# AstroEQ_PTH_V4_6.net
KiCad netlist of a schematic drawn in EAGLE
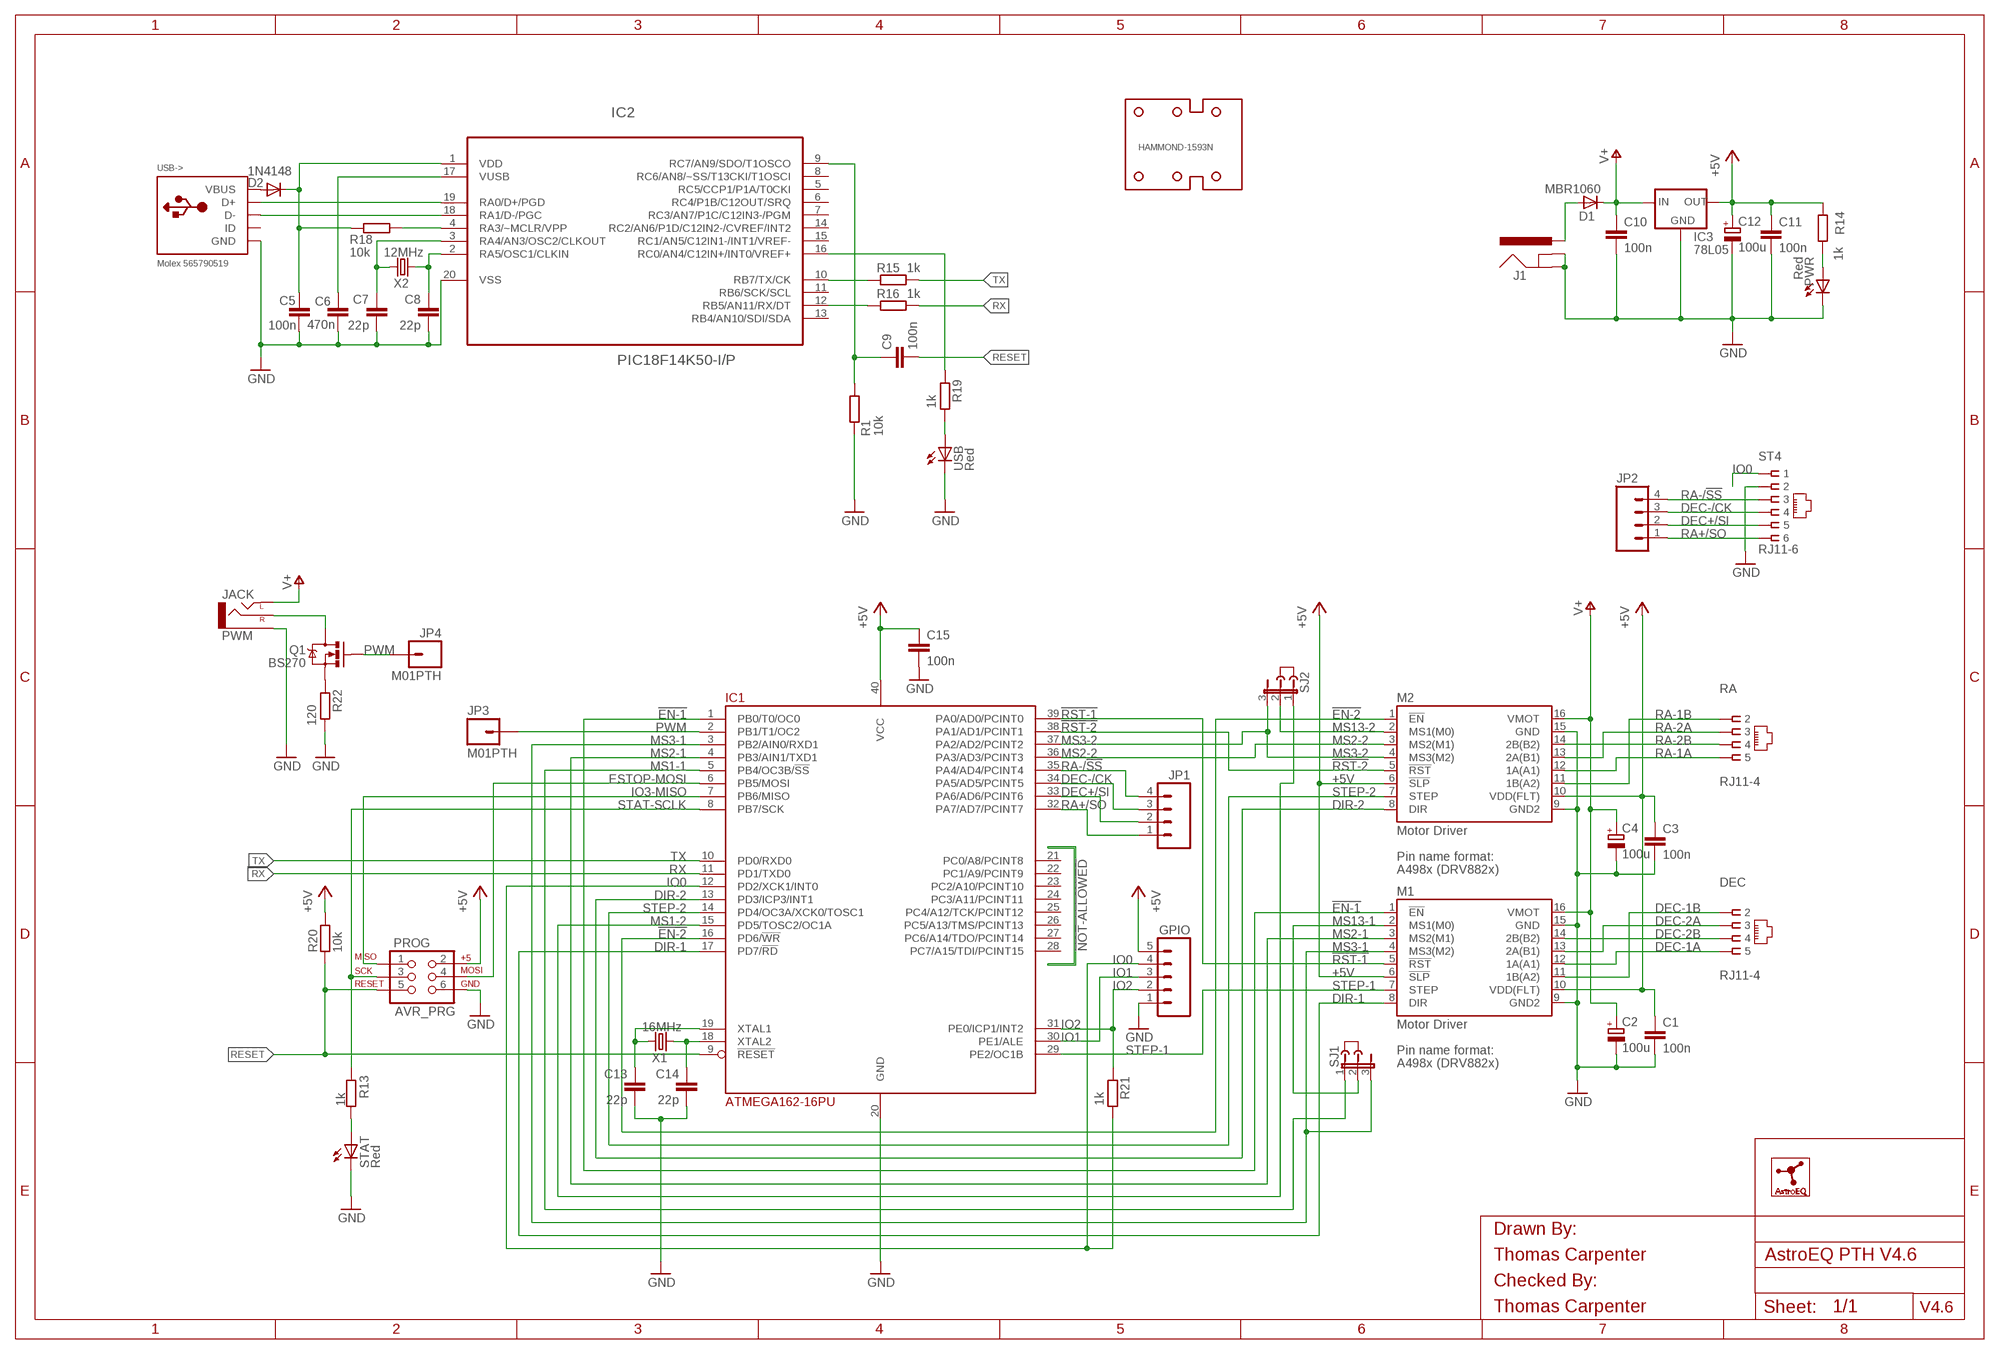
[diagram p0: schematic, sheet 1]

(export (version "E")
  (design (tool "Eeschema 10.0.6"))
  (components
    (comp (ref "C1")
      (value "100n")
      (footprint "eagle-import:C025-024X044")
      (fields (field (name "MF") "AVX") (field (name "MPN") "SR205C104KAR"))
      (libsource (lib "eagle-import") (part "C-EU025-024X044"))
    )
    (comp (ref "C2")
      (value "100u")
      (footprint "eagle-import:E2,5-7")
      (fields (field (name "MF") "MULTICOMP") (field (name "MPN") "MCGPR25V107M6.3X11"))
      (libsource (lib "eagle-import") (part "CPOL-EUE2.5-7"))
    )
    (comp (ref "C3")
      (value "100n")
      (footprint "eagle-import:C025-024X044")
      (fields (field (name "MF") "AVX") (field (name "MPN") "SR205C104KAR"))
      (libsource (lib "eagle-import") (part "C-EU025-024X044"))
    )
    (comp (ref "C4")
      (value "100u")
      (footprint "eagle-import:E2,5-7")
      (fields (field (name "MF") "MULTICOMP") (field (name "MPN") "MCGPR25V107M6.3X11"))
      (libsource (lib "eagle-import") (part "CPOL-EUE2.5-7"))
    )
    (comp (ref "C5")
      (value "100n")
      (footprint "eagle-import:C025-024X044")
      (fields (field (name "MF") "AVX") (field (name "MPN") "SR205C104KAR"))
      (libsource (lib "eagle-import") (part "C-EU025-024X044"))
    )
    (comp (ref "C6")
      (value "470n")
      (footprint "eagle-import:C025-024X044")
      (fields (field (name "MF") "KEMET") (field (name "MPN") "C320C474M5U5TA"))
      (libsource (lib "eagle-import") (part "C-EU025-024X044"))
    )
    (comp (ref "C7")
      (value "22p")
      (footprint "eagle-import:C025-024X044")
      (fields (field (name "MF") "AVX") (field (name "MPN") "SR151A220JAR"))
      (libsource (lib "eagle-import") (part "C-EU025-024X044"))
    )
    (comp (ref "C8")
      (value "22p")
      (footprint "eagle-import:C025-024X044")
      (fields (field (name "MF") "AVX") (field (name "MPN") "SR151A220JAR"))
      (libsource (lib "eagle-import") (part "C-EU025-024X044"))
    )
    (comp (ref "C9")
      (value "100n")
      (footprint "eagle-import:C025-024X044")
      (fields (field (name "MF") "AVX") (field (name "MPN") "SR205C104KAR"))
      (libsource (lib "eagle-import") (part "C-EU025-024X044"))
    )
    (comp (ref "C10")
      (value "100n")
      (footprint "eagle-import:C025-024X044")
      (fields (field (name "MF") "AVX") (field (name "MPN") "SR205C104KAR"))
      (libsource (lib "eagle-import") (part "C-EU025-024X044"))
    )
    (comp (ref "C11")
      (value "100n")
      (footprint "eagle-import:C025-024X044")
      (fields (field (name "MF") "AVX") (field (name "MPN") "SR205C104KAR"))
      (libsource (lib "eagle-import") (part "C-EU025-024X044"))
    )
    (comp (ref "C12")
      (value "100u")
      (footprint "eagle-import:E2,5-7")
      (fields (field (name "MF") "MULTICOMP") (field (name "MPN") "MCGPR25V107M6.3X11"))
      (libsource (lib "eagle-import") (part "CPOL-EUE2.5-7"))
    )
    (comp (ref "C13")
      (value "22p")
      (footprint "eagle-import:C025-024X044")
      (fields (field (name "MF") "AVX") (field (name "MPN") "SR151A220JAR"))
      (libsource (lib "eagle-import") (part "C-EU025-024X044"))
    )
    (comp (ref "C14")
      (value "22p")
      (footprint "eagle-import:C025-024X044")
      (fields (field (name "MF") "AVX") (field (name "MPN") "SR151A220JAR"))
      (libsource (lib "eagle-import") (part "C-EU025-024X044"))
    )
    (comp (ref "C15")
      (value "100n")
      (footprint "eagle-import:C025-024X044")
      (fields (field (name "MF") "AVX") (field (name "MPN") "SR205C104KAR"))
      (libsource (lib "eagle-import") (part "C-EU025-024X044"))
    )
    (comp (ref "D1")
      (value "MBR1060")
      (footprint "eagle-import:C221B1A")
      (fields (field (name "MF") "MULTICOMP"))
      (libsource (lib "eagle-import") (part "MUR820"))
    )
    (comp (ref "D2")
      (value "1N4148")
      (footprint "eagle-import:DIODE-1N4148")
      (fields (field (name "MF") "MULTICOMP") (field (name "MPN") "1N4148."))
      (libsource (lib "eagle-import") (part "DIODE1N4148"))
    )
    (comp (ref "DEC")
      (value "RJ11-4")
      (footprint "eagle-import:RJ11-NO_SHIELD-4")
      (fields (field (name "MF") "MOLEX") (field (name "MPN") "95501-2641"))
      (libsource (lib "eagle-import") (part "RJ11-4"))
    )
    (comp (ref "GPIO")
      (value "M05PTH")
      (footprint "eagle-import:1X05")
      (fields (field (name "MF") "CYNERGY3") (field (name "MPN") "SSF211X050"))
      (libsource (lib "eagle-import") (part "M05PTH"))
    )
    (comp (ref "HAMMOND-1593N")
      (value "HAMMOND-1593N-4HOLE")
      (footprint "eagle-import:HAMMOND-1593N4HOLES")
      (fields (field (name "MF") "HAMMOND") (field (name "MPN") "1593NBK"))
      (libsource (lib "eagle-import") (part "HAMMOND-1593N-4HOLE"))
    )
    (comp (ref "IC1")
      (value "ATMEGA162-16PU")
      (footprint "eagle-import:DIL40")
      (fields (field (name "MF") "ATMEL"))
      (libsource (lib "eagle-import") (part "ATMEGA162-16PU"))
    )
    (comp (ref "IC2")
      (value "PIC18F14K50-I/P")
      (footprint "eagle-import:DIL20")
      (fields (field (name "MF") "MICROCHIP"))
      (libsource (lib "eagle-import") (part "PIC18F14K50-I/P"))
    )
    (comp (ref "IC3")
      (value "78L05")
      (footprint "eagle-import:TO-92")
      (fields (field (name "MF") "FAIRCHILD SEMICONDUCTOR") (field (name "MPN") "LM78L05ACZX"))
      (libsource (lib "eagle-import") (part "V_REG_78XXTO-92"))
    )
    (comp (ref "J1")
      (value "POWER_JACKPTH")
      (footprint "eagle-import:POWER_JACK_PTH")
      (fields (field (name "MF") "MULTICOMP") (field (name "MPN") "MJ-179PH"))
      (libsource (lib "eagle-import") (part "POWER_JACKPTH"))
    )
    (comp (ref "J2")
      (value "JUMPER")
      (footprint "eagle-import:JUMP")
      (libsource (lib "eagle-import") (part "JUMPER"))
    )
    (comp (ref "J3")
      (value "JUMPER")
      (footprint "eagle-import:JUMP")
      (libsource (lib "eagle-import") (part "JUMPER"))
    )
    (comp (ref "JP1")
      (value "M04PTH")
      (footprint "eagle-import:1X04")
      (libsource (lib "eagle-import") (part "M04PTH"))
    )
    (comp (ref "JP2")
      (value "M04PTH")
      (footprint "eagle-import:1X04")
      (libsource (lib "eagle-import") (part "M04PTH"))
    )
    (comp (ref "JP3")
      (value "M01PTH")
      (footprint "eagle-import:1X01")
      (libsource (lib "eagle-import") (part "M01PTH"))
    )
    (comp (ref "JP4")
      (value "M01PTH")
      (footprint "eagle-import:1X01")
      (libsource (lib "eagle-import") (part "M01PTH"))
    )
    (comp (ref "LOGO1")
      (value "ASTROEQ5MM")
      (footprint "eagle-import:ASTROEQ-SMALL")
      (libsource (lib "eagle-import") (part "ASTROEQ5MM"))
    )
    (comp (ref "M1")
      (value "Motor Driver")
      (footprint "eagle-import:DIP16-W")
      (fields (field (name "MF") "SAMTEC") (field (name "MPN") "CES-116-01-T-S"))
      (libsource (lib "eagle-import") (part "A4983CARRIER"))
    )
    (comp (ref "M2")
      (value "Motor Driver")
      (footprint "eagle-import:DIP16-W")
      (fields (field (name "MF") "SAMTEC") (field (name "MPN") "CES-116-01-T-S"))
      (libsource (lib "eagle-import") (part "A4983CARRIER"))
    )
    (comp (ref "PROG")
      (value "AVR_PRG")
      (footprint "eagle-import:2X3")
      (fields (field (name "MF") "TE CONNECTIVITY / AMP") (field (name "MPN") "826632-3"))
      (libsource (lib "eagle-import") (part "AVR_SPI_PRG_6PTH"))
    )
    (comp (ref "PWM")
      (value "JACK")
      (footprint "eagle-import:AUDIO-JACK")
      (fields (field (name "MF") "CLIFF ELECTRONIC COMPONENTS") (field (name "MPN") "FC68131"))
      (libsource (lib "eagle-import") (part "AUDIO-JACKPTH"))
    )
    (comp (ref "PWR")
      (value "Red")
      (footprint "eagle-import:LED3MM")
      (fields (field (name "MF") "KINGBRIGHT") (field (name "MPN") "L-424HDT"))
      (libsource (lib "eagle-import") (part "LED3MM"))
    )
    (comp (ref "Q1")
      (value "BS270")
      (footprint "eagle-import:TO-92")
      (fields (field (name "MF") "FAIRCHILD SEMICONDUCTOR"))
      (libsource (lib "eagle-import") (part "MOSFET-NCHANNELPTH"))
    )
    (comp (ref "R1")
      (value "10k")
      (footprint "eagle-import:0204_7")
      (fields (field (name "MF") "MULTICOMP") (field (name "MPN") "MF12 10K"))
      (libsource (lib "eagle-import") (part "R-EU_0204/7"))
    )
    (comp (ref "R13")
      (value "1k")
      (footprint "eagle-import:0204_7")
      (fields (field (name "MF") "MULTICOMP") (field (name "MPN") "MF12 1K"))
      (libsource (lib "eagle-import") (part "R-EU_0204/7"))
    )
    (comp (ref "R14")
      (value "1k")
      (footprint "eagle-import:0204_7")
      (fields (field (name "MF") "MULTICOMP") (field (name "MPN") "MF12 1K"))
      (libsource (lib "eagle-import") (part "R-EU_0204/7"))
    )
    (comp (ref "R15")
      (value "1k")
      (footprint "eagle-import:0204_7")
      (fields (field (name "MF") "MULTICOMP") (field (name "MPN") "MF12 1K"))
      (libsource (lib "eagle-import") (part "R-EU_0204/7"))
    )
    (comp (ref "R16")
      (value "1k")
      (footprint "eagle-import:0204_7")
      (fields (field (name "MF") "MULTICOMP") (field (name "MPN") "MF12 1K"))
      (libsource (lib "eagle-import") (part "R-EU_0204/7"))
    )
    (comp (ref "R18")
      (value "10k")
      (footprint "eagle-import:0204_7")
      (fields (field (name "MF") "MULTICOMP") (field (name "MPN") "MF12 10K"))
      (libsource (lib "eagle-import") (part "R-EU_0204/7"))
    )
    (comp (ref "R19")
      (value "1k")
      (footprint "eagle-import:0204_7")
      (fields (field (name "MF") "MULTICOMP") (field (name "MPN") "MF12 1K"))
      (libsource (lib "eagle-import") (part "R-EU_0204/7"))
    )
    (comp (ref "R20")
      (value "10k")
      (footprint "eagle-import:0204_7")
      (fields (field (name "MF") "MULTICOMP") (field (name "MPN") "MF12 10K"))
      (libsource (lib "eagle-import") (part "R-EU_0204/7"))
    )
    (comp (ref "R21")
      (value "1k")
      (footprint "eagle-import:0204_7")
      (fields (field (name "MF") "MULTICOMP") (field (name "MPN") "MF12 1K"))
      (libsource (lib "eagle-import") (part "R-EU_0204/7"))
    )
    (comp (ref "R22")
      (value "120")
      (footprint "eagle-import:0204_7")
      (fields (field (name "MF") "MULTICOMP") (field (name "MPN") "MF12 120R"))
      (libsource (lib "eagle-import") (part "R-EU_0204/7"))
    )
    (comp (ref "RA")
      (value "RJ11-4")
      (footprint "eagle-import:RJ11-NO_SHIELD-4")
      (fields (field (name "MF") "MOLEX") (field (name "MPN") "95501-2641"))
      (libsource (lib "eagle-import") (part "RJ11-4"))
    )
    (comp (ref "SJ1")
      (value "JP2E")
      (footprint "eagle-import:JP2")
      (libsource (lib "eagle-import") (part "JP2E"))
    )
    (comp (ref "SJ2")
      (value "JP2EL")
      (footprint "eagle-import:JP2L")
      (libsource (lib "eagle-import") (part "JP2EL"))
    )
    (comp (ref "ST4")
      (value "RJ11-6")
      (footprint "eagle-import:RJ11-NO_SHIELD")
      (fields
        (field (name "MF") "TYCO ELECTRONICS")
        (field (name "MPN") "RJ11-2L-B")
        (field (name "MF_1") "MOLEX")
        (field (name "MPN_1") "95501-2661")
        (field (name "OC_FARNELL") "1536490")
      )
      (libsource (lib "eagle-import") (part "RJ11-2L-B"))
    )
    (comp (ref "STAT")
      (value "Red")
      (footprint "eagle-import:LED3MM")
      (fields (field (name "MF") "KINGBRIGHT") (field (name "MPN") "L-424HDT"))
      (libsource (lib "eagle-import") (part "LED3MM"))
    )
    (comp (ref "USB")
      (value "Red")
      (footprint "eagle-import:LED3MM")
      (fields (field (name "MF") "KINGBRIGHT") (field (name "MPN") "L-424HDT"))
      (libsource (lib "eagle-import") (part "LED3MM"))
    )
    (comp (ref "USB->")
      (value "Molex 565790519")
      (footprint "eagle-import:USB-MINIB-THM-MOLEX")
      (fields (field (name "MF") "MOLEX") (field (name "MPN") "565790519"))
      (libsource (lib "eagle-import") (part "USBMOLEX"))
    )
    (comp (ref "X1")
      (value "16MHz")
      (footprint "eagle-import:HC49US")
      (fields (field (name "MF") "TXC") (field (name "MPN") "9B-16.000MEEJ-B"))
      (libsource (lib "eagle-import") (part "CRYSTALHC49US"))
    )
    (comp (ref "X2")
      (value "12MHz")
      (footprint "eagle-import:HC49US")
      (fields (field (name "MF") "TXC") (field (name "MPN") "9B-12.000MAAJ-B"))
      (libsource (lib "eagle-import") (part "CRYSTALHC49US"))
    )
  )
  (nets
    (net (code "1") (name "+5V") (class "Default")
      (node (ref "C1") (pin "1") (pinfunction "1_1") (pintype "passive"))
      (node (ref "C11") (pin "1") (pinfunction "1_1") (pintype "passive"))
      (node (ref "C12") (pin "+") (pinfunction "+_+") (pintype "passive"))
      (node (ref "C15") (pin "1") (pinfunction "1_1") (pintype "passive"))
      (node (ref "C3") (pin "1") (pinfunction "1_1") (pintype "passive"))
      (node (ref "GPIO") (pin "5") (pinfunction "5_5") (pintype "passive"))
      (node (ref "IC1") (pin "40") (pinfunction "VCC_40") (pintype "power_in"))
      (node (ref "IC3") (pin "1") (pinfunction "OUT_1") (pintype "power_in"))
      (node (ref "M1") (pin "10") (pinfunction "VDD(FLT)_10") (pintype "power_in"))
      (node (ref "M1") (pin "6") (pinfunction "~{SLP}_6") (pintype "input"))
      (node (ref "M2") (pin "10") (pinfunction "VDD(FLT)_10") (pintype "power_in"))
      (node (ref "M2") (pin "6") (pinfunction "~{SLP}_6") (pintype "input"))
      (node (ref "PROG") (pin "2") (pinfunction "2_2") (pintype "passive"))
      (node (ref "R14") (pin "1") (pinfunction "1_1") (pintype "passive"))
      (node (ref "R20") (pin "2") (pinfunction "2_2") (pintype "passive"))
    )
    (net (code "2") (name "/DEC+{slash}SI") (class "Default")
      (node (ref "IC1") (pin "33") (pinfunction "PA6/AD6/PCINT6_33") (pintype "bidirectional"))
      (node (ref "JP1") (pin "2") (pinfunction "2_2") (pintype "passive"))
      (node (ref "JP2") (pin "2") (pinfunction "2_2") (pintype "passive"))
      (node (ref "ST4") (pin "5") (pinfunction "5_5") (pintype "passive"))
    )
    (net (code "3") (name "/DEC-1A") (class "Default")
      (node (ref "DEC") (pin "5") (pinfunction "5_5") (pintype "passive"))
      (node (ref "M1") (pin "12") (pinfunction "1A(A1)_12") (pintype "output"))
    )
    (net (code "4") (name "/DEC-1B") (class "Default")
      (node (ref "DEC") (pin "2") (pinfunction "2_2") (pintype "passive"))
      (node (ref "M1") (pin "11") (pinfunction "1B(A2)_11") (pintype "output"))
    )
    (net (code "5") (name "/DEC-2A") (class "Default")
      (node (ref "DEC") (pin "3") (pinfunction "3_3") (pintype "passive"))
      (node (ref "M1") (pin "13") (pinfunction "2A(B1)_13") (pintype "output"))
    )
    (net (code "6") (name "/DEC-2B") (class "Default")
      (node (ref "DEC") (pin "4") (pinfunction "4_4") (pintype "passive"))
      (node (ref "M1") (pin "14") (pinfunction "2B(B2)_14") (pintype "output"))
    )
    (net (code "7") (name "/DEC-{slash}CK") (class "Default")
      (node (ref "IC1") (pin "34") (pinfunction "PA5/AD5/PCINT5_34") (pintype "bidirectional"))
      (node (ref "JP1") (pin "3") (pinfunction "3_3") (pintype "passive"))
      (node (ref "JP2") (pin "3") (pinfunction "3_3") (pintype "passive"))
      (node (ref "ST4") (pin "4") (pinfunction "4_4") (pintype "passive"))
    )
    (net (code "8") (name "/DIR-1") (class "Default")
      (node (ref "IC1") (pin "17") (pinfunction "PD7/~{RD}_17") (pintype "bidirectional"))
      (node (ref "M1") (pin "8") (pinfunction "DIR_8") (pintype "input"))
    )
    (net (code "9") (name "/DIR-2") (class "Default")
      (node (ref "IC1") (pin "13") (pinfunction "PD3/ICP3/INT1_13") (pintype "bidirectional"))
      (node (ref "M2") (pin "8") (pinfunction "DIR_8") (pintype "input"))
    )
    (net (code "10") (name "/ESTOP-MOSI") (class "Default")
      (node (ref "IC1") (pin "6") (pinfunction "PB5/MOSI_6") (pintype "bidirectional"))
      (node (ref "PROG") (pin "4") (pinfunction "4_4") (pintype "passive"))
    )
    (net (code "11") (name "/IO0") (class "Default")
      (node (ref "GPIO") (pin "4") (pinfunction "4_4") (pintype "passive"))
      (node (ref "IC1") (pin "12") (pinfunction "PD2/XCK1/INT0_12") (pintype "bidirectional"))
      (node (ref "R21") (pin "1") (pinfunction "1_1") (pintype "passive"))
      (node (ref "ST4") (pin "1") (pinfunction "1_1") (pintype "passive"))
    )
    (net (code "12") (name "/IO1") (class "Default")
      (node (ref "GPIO") (pin "3") (pinfunction "3_3") (pintype "passive"))
      (node (ref "IC1") (pin "30") (pinfunction "PE1/ALE_30") (pintype "bidirectional"))
    )
    (net (code "13") (name "/IO2") (class "Default")
      (node (ref "GPIO") (pin "2") (pinfunction "2_2") (pintype "passive"))
      (node (ref "IC1") (pin "31") (pinfunction "PE0/ICP1/INT2_31") (pintype "bidirectional"))
      (node (ref "R21") (pin "2") (pinfunction "2_2") (pintype "passive"))
    )
    (net (code "14") (name "/IO3-MISO") (class "Default")
      (node (ref "IC1") (pin "7") (pinfunction "PB6/MISO_7") (pintype "bidirectional"))
      (node (ref "PROG") (pin "1") (pinfunction "1_1") (pintype "passive"))
    )
    (net (code "15") (name "/MS1-1") (class "Default")
      (node (ref "IC1") (pin "5") (pinfunction "PB4/OC3B/~{SS}_5") (pintype "bidirectional"))
      (node (ref "SJ1") (pin "1") (pinfunction "1_1") (pintype "passive"))
    )
    (net (code "16") (name "/MS1-2") (class "Default")
      (node (ref "IC1") (pin "15") (pinfunction "PD5/TOSC2/OC1A_15") (pintype "bidirectional"))
      (node (ref "SJ2") (pin "1") (pinfunction "1_1") (pintype "passive"))
    )
    (net (code "17") (name "/MS2-1") (class "Default")
      (node (ref "IC1") (pin "4") (pinfunction "PB3/AIN1/TXD1_4") (pintype "bidirectional"))
      (node (ref "M1") (pin "3") (pinfunction "MS2(M1)_3") (pintype "input"))
    )
    (net (code "18") (name "/MS2-2") (class "Default")
      (node (ref "IC1") (pin "36") (pinfunction "PA3/AD3/PCINT3_36") (pintype "bidirectional"))
      (node (ref "M2") (pin "3") (pinfunction "MS2(M1)_3") (pintype "input"))
    )
    (net (code "19") (name "/MS3-1") (class "Default")
      (node (ref "IC1") (pin "3") (pinfunction "PB2/AIN0/RXD1_3") (pintype "bidirectional"))
      (node (ref "M1") (pin "4") (pinfunction "MS3(M2)_4") (pintype "input"))
      (node (ref "SJ1") (pin "3") (pinfunction "3_3") (pintype "passive"))
    )
    (net (code "20") (name "/MS3-2") (class "Default")
      (node (ref "IC1") (pin "37") (pinfunction "PA2/AD2/PCINT2_37") (pintype "bidirectional"))
      (node (ref "M2") (pin "4") (pinfunction "MS3(M2)_4") (pintype "input"))
      (node (ref "SJ2") (pin "3") (pinfunction "3_3") (pintype "passive"))
    )
    (net (code "21") (name "/MS13-1") (class "Default")
      (node (ref "M1") (pin "2") (pinfunction "MS1(M0)_2") (pintype "input"))
      (node (ref "SJ1") (pin "2") (pinfunction "2_2") (pintype "passive"))
    )
    (net (code "22") (name "/MS13-2") (class "Default")
      (node (ref "M2") (pin "2") (pinfunction "MS1(M0)_2") (pintype "input"))
      (node (ref "SJ2") (pin "2") (pinfunction "2_2") (pintype "passive"))
    )
    (net (code "23") (name "/PWM") (class "Default")
      (node (ref "IC1") (pin "2") (pinfunction "PB1/T1/OC2_2") (pintype "bidirectional"))
      (node (ref "JP3") (pin "1") (pinfunction "1_1") (pintype "passive"))
      (node (ref "JP4") (pin "1") (pinfunction "1_1") (pintype "passive"))
      (node (ref "Q1") (pin "2") (pinfunction "G_2") (pintype "passive"))
    )
    (net (code "24") (name "/RA+{slash}SO") (class "Default")
      (node (ref "IC1") (pin "32") (pinfunction "PA7/AD7/PCINT7_32") (pintype "bidirectional"))
      (node (ref "JP1") (pin "1") (pinfunction "1_1") (pintype "passive"))
      (node (ref "JP2") (pin "1") (pinfunction "1_1") (pintype "passive"))
      (node (ref "ST4") (pin "6") (pinfunction "6_6") (pintype "passive"))
    )
    (net (code "25") (name "/RA-1A") (class "Default")
      (node (ref "M2") (pin "12") (pinfunction "1A(A1)_12") (pintype "output"))
      (node (ref "RA") (pin "5") (pinfunction "5_5") (pintype "passive"))
    )
    (net (code "26") (name "/RA-1B") (class "Default")
      (node (ref "M2") (pin "11") (pinfunction "1B(A2)_11") (pintype "output"))
      (node (ref "RA") (pin "2") (pinfunction "2_2") (pintype "passive"))
    )
    (net (code "27") (name "/RA-2A") (class "Default")
      (node (ref "M2") (pin "13") (pinfunction "2A(B1)_13") (pintype "output"))
      (node (ref "RA") (pin "3") (pinfunction "3_3") (pintype "passive"))
    )
    (net (code "28") (name "/RA-2B") (class "Default")
      (node (ref "M2") (pin "14") (pinfunction "2B(B2)_14") (pintype "output"))
      (node (ref "RA") (pin "4") (pinfunction "4_4") (pintype "passive"))
    )
    (net (code "29") (name "/RA-{slash}~{SS}") (class "Default")
      (node (ref "IC1") (pin "35") (pinfunction "PA4/AD4/PCINT4_35") (pintype "bidirectional"))
      (node (ref "JP1") (pin "4") (pinfunction "4_4") (pintype "passive"))
      (node (ref "JP2") (pin "4") (pinfunction "4_4") (pintype "passive"))
      (node (ref "ST4") (pin "3") (pinfunction "3_3") (pintype "passive"))
    )
    (net (code "30") (name "/STAT-SCLK") (class "Default")
      (node (ref "IC1") (pin "8") (pinfunction "PB7/SCK_8") (pintype "bidirectional"))
      (node (ref "PROG") (pin "3") (pinfunction "3_3") (pintype "passive"))
      (node (ref "R13") (pin "1") (pinfunction "1_1") (pintype "passive"))
    )
    (net (code "31") (name "/STEP-1") (class "Default")
      (node (ref "IC1") (pin "29") (pinfunction "PE2/OC1B_29") (pintype "bidirectional"))
      (node (ref "M1") (pin "7") (pinfunction "STEP_7") (pintype "input"))
    )
    (net (code "32") (name "/STEP-2") (class "Default")
      (node (ref "IC1") (pin "14") (pinfunction "PD4/OC3A/XCK0/TOSC1_14") (pintype "bidirectional"))
      (node (ref "M2") (pin "7") (pinfunction "STEP_7") (pintype "input"))
    )
    (net (code "33") (name "/~{EN-1}") (class "Default")
      (node (ref "IC1") (pin "1") (pinfunction "PB0/T0/OC0_1") (pintype "bidirectional"))
      (node (ref "M1") (pin "1") (pinfunction "~{EN}_1") (pintype "input"))
    )
    (net (code "34") (name "/~{EN-2}") (class "Default")
      (node (ref "IC1") (pin "16") (pinfunction "PD6/~{WR}_16") (pintype "bidirectional"))
      (node (ref "M2") (pin "1") (pinfunction "~{EN}_1") (pintype "input"))
    )
    (net (code "36") (name "/~{RST-1}") (class "Default")
      (node (ref "IC1") (pin "39") (pinfunction "PA0/AD0/PCINT0_39") (pintype "bidirectional"))
      (node (ref "M1") (pin "5") (pinfunction "~{RST}_5") (pintype "input"))
    )
    (net (code "37") (name "/~{RST-2}") (class "Default")
      (node (ref "IC1") (pin "38") (pinfunction "PA1/AD1/PCINT1_38") (pintype "bidirectional"))
      (node (ref "M2") (pin "5") (pinfunction "~{RST}_5") (pintype "input"))
    )
    (net (code "38") (name "GND") (class "Default")
      (node (ref "C1") (pin "2") (pinfunction "2_2") (pintype "passive"))
      (node (ref "C10") (pin "2") (pinfunction "2_2") (pintype "passive"))
      (node (ref "C11") (pin "2") (pinfunction "2_2") (pintype "passive"))
      (node (ref "C12") (pin "-") (pinfunction "-_-") (pintype "passive"))
      (node (ref "C13") (pin "2") (pinfunction "2_2") (pintype "passive"))
      (node (ref "C14") (pin "2") (pinfunction "2_2") (pintype "passive"))
      (node (ref "C15") (pin "2") (pinfunction "2_2") (pintype "passive"))
      (node (ref "C2") (pin "-") (pinfunction "-_-") (pintype "passive"))
      (node (ref "C3") (pin "2") (pinfunction "2_2") (pintype "passive"))
      (node (ref "C4") (pin "-") (pinfunction "-_-") (pintype "passive"))
      (node (ref "C5") (pin "2") (pinfunction "2_2") (pintype "passive"))
      (node (ref "C6") (pin "1") (pinfunction "1_1") (pintype "passive"))
      (node (ref "C7") (pin "2") (pinfunction "2_2") (pintype "passive"))
      (node (ref "C8") (pin "2") (pinfunction "2_2") (pintype "passive"))
      (node (ref "GPIO") (pin "1") (pinfunction "1_1") (pintype "passive"))
      (node (ref "IC1") (pin "20") (pinfunction "GND_20") (pintype "power_in"))
      (node (ref "IC2") (pin "20") (pinfunction "VSS_20") (pintype "power_in"))
      (node (ref "IC3") (pin "2") (pinfunction "GND_2") (pintype "input"))
      (node (ref "J1") (pin "GND") (pinfunction "GND_GND") (pintype "bidirectional"))
      (node (ref "J1") (pin "GNDBREAK") (pinfunction "GNDBREAK_GNDBREAK") (pintype "bidirectional"))
      (node (ref "M1") (pin "15") (pinfunction "GND_15") (pintype "power_in"))
      (node (ref "M1") (pin "9") (pinfunction "GND2_9") (pintype "power_in"))
      (node (ref "M2") (pin "15") (pinfunction "GND_15") (pintype "power_in"))
      (node (ref "M2") (pin "9") (pinfunction "GND2_9") (pintype "power_in"))
      (node (ref "PROG") (pin "6") (pinfunction "6_6") (pintype "passive"))
      (node (ref "PWM") (pin "SLEEVE") (pinfunction "SLEEVE_SLEEVE") (pintype "bidirectional"))
      (node (ref "PWR") (pin "K") (pinfunction "C_K") (pintype "passive"))
      (node (ref "R1") (pin "2") (pinfunction "2_2") (pintype "passive"))
      (node (ref "R22") (pin "1") (pinfunction "1_1") (pintype "passive"))
      (node (ref "ST4") (pin "2") (pinfunction "2_2") (pintype "passive"))
      (node (ref "STAT") (pin "K") (pinfunction "C_K") (pintype "passive"))
      (node (ref "USB") (pin "K") (pinfunction "C_K") (pintype "passive"))
      (node (ref "USB->") (pin "GND") (pinfunction "GND_GND") (pintype "power_in"))
    )
    (net (code "39") (name "Net-(D1-PadA)") (class "Default")
      (node (ref "D1") (pin "A") (pinfunction "A_A") (pintype "passive"))
      (node (ref "J1") (pin "PWR") (pinfunction "PWR_PWR") (pintype "bidirectional"))
    )
    (net (code "40") (name "Net-(D2-PadA)") (class "Default")
      (node (ref "D2") (pin "A") (pinfunction "A_A") (pintype "passive"))
      (node (ref "USB->") (pin "VBUS") (pinfunction "VBUS_VBUS") (pintype "power_in"))
    )
    (net (code "41") (name "Net-(IC1-XTAL1)") (class "Default")
      (node (ref "C13") (pin "1") (pinfunction "1_1") (pintype "passive"))
      (node (ref "IC1") (pin "19") (pinfunction "XTAL1_19") (pintype "input"))
      (node (ref "X1") (pin "2") (pinfunction "2_2") (pintype "passive"))
    )
    (net (code "42") (name "Net-(IC1-XTAL2)") (class "Default")
      (node (ref "C14") (pin "1") (pinfunction "1_1") (pintype "passive"))
      (node (ref "IC1") (pin "18") (pinfunction "XTAL2_18") (pintype "input"))
      (node (ref "X1") (pin "1") (pinfunction "1_1") (pintype "passive"))
    )
    (net (code "43") (name "Net-(IC2-RA0{slash}D+{slash}PGD)") (class "Default")
      (node (ref "IC2") (pin "19") (pinfunction "RA0/D+/PGD_19") (pintype "bidirectional"))
      (node (ref "USB->") (pin "D+") (pinfunction "D+_D+") (pintype "bidirectional"))
    )
    (net (code "44") (name "Net-(IC2-RA1{slash}D-{slash}PGC)") (class "Default")
      (node (ref "IC2") (pin "18") (pinfunction "RA1/D-/PGC_18") (pintype "bidirectional"))
      (node (ref "USB->") (pin "D-") (pinfunction "D-_D-") (pintype "bidirectional"))
    )
    (net (code "45") (name "Net-(IC2-RA3{slash}~{MCLR{slash}VPP})") (class "Default")
      (node (ref "IC2") (pin "4") (pinfunction "RA3/~{MCLR/VPP}_4") (pintype "input"))
      (node (ref "R18") (pin "1") (pinfunction "1_1") (pintype "passive"))
    )
    (net (code "46") (name "Net-(IC2-RA4{slash}AN3{slash}OSC2{slash}CLKOUT)") (class "Default")
      (node (ref "C7") (pin "1") (pinfunction "1_1") (pintype "passive"))
      (node (ref "IC2") (pin "3") (pinfunction "RA4/AN3/OSC2/CLKOUT_3") (pintype "bidirectional"))
      (node (ref "X2") (pin "2") (pinfunction "2_2") (pintype "passive"))
    )
    (net (code "47") (name "Net-(IC2-RA5{slash}OSC1{slash}CLKIN)") (class "Default")
      (node (ref "C8") (pin "1") (pinfunction "1_1") (pintype "passive"))
      (node (ref "IC2") (pin "2") (pinfunction "RA5/OSC1/CLKIN_2") (pintype "bidirectional"))
      (node (ref "X2") (pin "1") (pinfunction "1_1") (pintype "passive"))
    )
    (net (code "48") (name "Net-(IC2-RB5{slash}AN11{slash}RX{slash}DT)") (class "Default")
      (node (ref "IC2") (pin "12") (pinfunction "RB5/AN11/RX/DT_12") (pintype "bidirectional"))
      (node (ref "R16") (pin "2") (pinfunction "2_2") (pintype "passive"))
    )
    (net (code "49") (name "Net-(IC2-RB7{slash}TX{slash}CK)") (class "Default")
      (node (ref "IC2") (pin "10") (pinfunction "RB7/TX/CK_10") (pintype "bidirectional"))
      (node (ref "R15") (pin "2") (pinfunction "2_2") (pintype "passive"))
    )
    (net (code "50") (name "Net-(IC2-RC0{slash}AN4{slash}C12IN+{slash}INT0{slash}VREF+)") (class "Default")
      (node (ref "IC2") (pin "16") (pinfunction "RC0/AN4/C12IN+/INT0/VREF+_16") (pintype "bidirectional"))
      (node (ref "R19") (pin "2") (pinfunction "2_2") (pintype "passive"))
    )
    (net (code "51") (name "Net-(IC2-RC7{slash}AN9{slash}SDO{slash}T1OSCO)") (class "Default")
      (node (ref "C9") (pin "1") (pinfunction "1_1") (pintype "passive"))
      (node (ref "IC2") (pin "9") (pinfunction "RC7/AN9/SDO/T1OSCO_9") (pintype "bidirectional"))
      (node (ref "R1") (pin "1") (pinfunction "1_1") (pintype "passive"))
    )
    (net (code "52") (name "Net-(IC2-VDD)") (class "Default")
      (node (ref "C5") (pin "1") (pinfunction "1_1") (pintype "passive"))
      (node (ref "D2") (pin "C") (pinfunction "C_C") (pintype "passive"))
      (node (ref "IC2") (pin "1") (pinfunction "VDD_1") (pintype "power_in"))
      (node (ref "R18") (pin "2") (pinfunction "2_2") (pintype "passive"))
    )
    (net (code "53") (name "Net-(IC2-VUSB)") (class "Default")
      (node (ref "C6") (pin "2") (pinfunction "2_2") (pintype "passive"))
      (node (ref "IC2") (pin "17") (pinfunction "VUSB_17") (pintype "power_in"))
    )
    (net (code "54") (name "Net-(PWM-RIGHT)") (class "Default")
      (node (ref "PWM") (pin "RING") (pinfunction "RIGHT_RING") (pintype "bidirectional"))
      (node (ref "Q1") (pin "1") (pinfunction "D_1") (pintype "passive"))
    )
    (net (code "55") (name "Net-(PWR-PadA)") (class "Default")
      (node (ref "PWR") (pin "A") (pinfunction "A_A") (pintype "passive"))
      (node (ref "R14") (pin "2") (pinfunction "2_2") (pintype "passive"))
    )
    (net (code "56") (name "Net-(Q1-S)") (class "Default")
      (node (ref "Q1") (pin "3") (pinfunction "S_3") (pintype "passive"))
      (node (ref "R22") (pin "2") (pinfunction "2_2") (pintype "passive"))
    )
    (net (code "57") (name "Net-(R13-Pad2)") (class "Default")
      (node (ref "R13") (pin "2") (pinfunction "2_2") (pintype "passive"))
      (node (ref "STAT") (pin "A") (pinfunction "A_A") (pintype "passive"))
    )
    (net (code "58") (name "Net-(R19-Pad1)") (class "Default")
      (node (ref "R19") (pin "1") (pinfunction "1_1") (pintype "passive"))
      (node (ref "USB") (pin "A") (pinfunction "A_A") (pintype "passive"))
    )
    (net (code "59") (name "RESET") (class "Default")
      (node (ref "C9") (pin "2") (pinfunction "2_2") (pintype "passive"))
      (node (ref "IC1") (pin "9") (pinfunction "~{RESET}_9") (pintype "input"))
      (node (ref "PROG") (pin "5") (pinfunction "5_5") (pintype "passive"))
      (node (ref "R20") (pin "1") (pinfunction "1_1") (pintype "passive"))
    )
    (net (code "60") (name "RX") (class "Default")
      (node (ref "IC1") (pin "11") (pinfunction "PD1/TXD0_11") (pintype "bidirectional"))
      (node (ref "R16") (pin "1") (pinfunction "1_1") (pintype "passive"))
    )
    (net (code "61") (name "TX") (class "Default")
      (node (ref "IC1") (pin "10") (pinfunction "PD0/RXD0_10") (pintype "bidirectional"))
      (node (ref "R15") (pin "1") (pinfunction "1_1") (pintype "passive"))
    )
    (net (code "62") (name "V+") (class "Default")
      (node (ref "C10") (pin "1") (pinfunction "1_1") (pintype "passive"))
      (node (ref "C2") (pin "+") (pinfunction "+_+") (pintype "passive"))
      (node (ref "C4") (pin "+") (pinfunction "+_+") (pintype "passive"))
      (node (ref "D1") (pin "C") (pinfunction "C_C") (pintype "passive"))
      (node (ref "IC3") (pin "3") (pinfunction "IN_3") (pintype "input"))
      (node (ref "M1") (pin "16") (pinfunction "VMOT_16") (pintype "power_in"))
      (node (ref "M2") (pin "16") (pinfunction "VMOT_16") (pintype "power_in"))
      (node (ref "PWM") (pin "TIP") (pinfunction "LEFT_TIP") (pintype "bidirectional"))
    )
    (net (code "63") (name "unconnected-(IC1-PC0{slash}A8{slash}PCINT8-Pad21)") (class "Default")
      (node (ref "IC1") (pin "21") (pinfunction "PC0/A8/PCINT8_21") (pintype "bidirectional"))
    )
    (net (code "64") (name "unconnected-(IC1-PC1{slash}A9{slash}PCINT9-Pad22)") (class "Default")
      (node (ref "IC1") (pin "22") (pinfunction "PC1/A9/PCINT9_22") (pintype "bidirectional"))
    )
    (net (code "65") (name "unconnected-(IC1-PC2{slash}A10{slash}PCINT10-Pad23)") (class "Default")
      (node (ref "IC1") (pin "23") (pinfunction "PC2/A10/PCINT10_23") (pintype "bidirectional"))
    )
    (net (code "66") (name "unconnected-(IC1-PC3{slash}A11{slash}PCINT11-Pad24)") (class "Default")
      (node (ref "IC1") (pin "24") (pinfunction "PC3/A11/PCINT11_24") (pintype "bidirectional"))
    )
    (net (code "67") (name "unconnected-(IC1-PC4{slash}A12{slash}TCK{slash}PCINT12-Pad25)") (class "Default")
      (node (ref "IC1") (pin "25") (pinfunction "PC4/A12/TCK/PCINT12_25") (pintype "bidirectional"))
    )
    (net (code "68") (name "unconnected-(IC1-PC5{slash}A13{slash}TMS{slash}PCINT13-Pad26)") (class "Default")
      (node (ref "IC1") (pin "26") (pinfunction "PC5/A13/TMS/PCINT13_26") (pintype "bidirectional"))
    )
    (net (code "69") (name "unconnected-(IC1-PC6{slash}A14{slash}TDO{slash}PCINT14-Pad27)") (class "Default")
      (node (ref "IC1") (pin "27") (pinfunction "PC6/A14/TDO/PCINT14_27") (pintype "bidirectional"))
    )
    (net (code "70") (name "unconnected-(IC1-PC7{slash}A15{slash}TDI{slash}PCINT15-Pad28)") (class "Default")
      (node (ref "IC1") (pin "28") (pinfunction "PC7/A15/TDI/PCINT15_28") (pintype "bidirectional"))
    )
    (net (code "71") (name "unconnected-(IC2-RB4{slash}AN10{slash}SDI{slash}SDA-Pad13)") (class "Default")
      (node (ref "IC2") (pin "13") (pinfunction "RB4/AN10/SDI/SDA_13") (pintype "bidirectional"))
    )
    (net (code "72") (name "unconnected-(IC2-RB6{slash}SCK{slash}SCL-Pad11)") (class "Default")
      (node (ref "IC2") (pin "11") (pinfunction "RB6/SCK/SCL_11") (pintype "bidirectional"))
    )
    (net (code "73") (name "unconnected-(IC2-RC1{slash}AN5{slash}C12IN1-{slash}INT1{slash}VREF--Pad15)") (class "Default")
      (node (ref "IC2") (pin "15") (pinfunction "RC1/AN5/C12IN1-/INT1/VREF-_15") (pintype "bidirectional"))
    )
    (net (code "74") (name "unconnected-(IC2-RC2{slash}AN6{slash}P1D{slash}C12IN2-{slash}CVREF{slash}INT2-Pad14)") (class "Default")
      (node (ref "IC2") (pin "14") (pinfunction "RC2/AN6/P1D/C12IN2-/CVREF/INT2_14") (pintype "bidirectional"))
    )
    (net (code "75") (name "unconnected-(IC2-RC3{slash}AN7{slash}P1C{slash}C12IN3-{slash}PGM-Pad7)") (class "Default")
      (node (ref "IC2") (pin "7") (pinfunction "RC3/AN7/P1C/C12IN3-/PGM_7") (pintype "bidirectional"))
    )
    (net (code "76") (name "unconnected-(IC2-RC4{slash}P1B{slash}C12OUT{slash}SRQ-Pad6)") (class "Default")
      (node (ref "IC2") (pin "6") (pinfunction "RC4/P1B/C12OUT/SRQ_6") (pintype "bidirectional"))
    )
    (net (code "77") (name "unconnected-(IC2-RC5{slash}CCP1{slash}P1A{slash}T0CKI-Pad5)") (class "Default")
      (node (ref "IC2") (pin "5") (pinfunction "RC5/CCP1/P1A/T0CKI_5") (pintype "bidirectional"))
    )
    (net (code "78") (name "unconnected-(IC2-RC6{slash}AN8{slash}~{SS{slash}T13CKI{slash}T1OSCI}-Pad8)") (class "Default")
      (node (ref "IC2") (pin "8") (pinfunction "RC6/AN8/~{SS/T13CKI/T1OSCI}_8") (pintype "bidirectional"))
    )
    (net (code "79") (name "unconnected-(USB->-PadID)") (class "Default")
      (node (ref "USB->") (pin "ID") (pinfunction "ID_ID") (pintype "bidirectional"))
    )
  )
)
